# Sheet1.net
KiCad netlist of a schematic drawn in Altium Designer
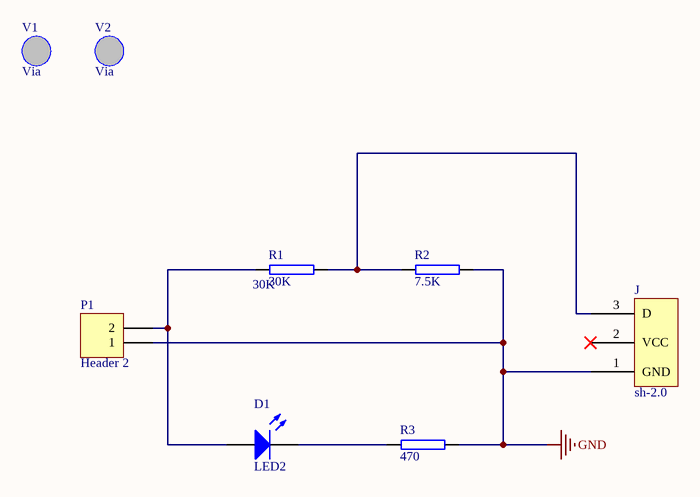
[diagram p0: Sheet1.SchDoc]

(export (version "E")
  (design (tool "Eeschema 10.0.6"))
  (components
    (comp (ref "D1")
      (value "LED2")
      (footprint "3.2X1.6X1.1")
      (description "Typical RED, GREEN, YELLOW, AMBER GaAs LED")
      (fields (field (name "PUBLISHER") "Altium Limited"))
      (libsource (lib "Miscellaneous Devices") (part "LED2"))
    )
    (comp (ref "J") (value "sh-2.0") (footprint "sh-2.0") (libsource (lib "zhangchong") (part "sh-2.0")))
    (comp (ref "P1")
      (value "Header 2")
      (footprint "DIP2")
      (description "Header, 2-Pin")
      (fields (field (name "PUBLISHER") "Altium Limited"))
      (libsource (lib "Miscellaneous Connectors") (part "Header 2"))
    )
    (comp (ref "R1")
      (value "30K")
      (footprint "Miscellaneous Devices:1608[0603]")
      (fields (field (name "ALTIUM_UNNAMED_1") "30K"))
      (libsource (lib "gupeng_sch") (part "RES"))
    )
    (comp (ref "R2")
      (value "7.5K")
      (footprint "Miscellaneous Devices:1608[0603]")
      (libsource (lib "gupeng_sch") (part "RES"))
    )
    (comp (ref "R3")
      (value "470")
      (footprint "Miscellaneous Devices:1608[0603]")
      (libsource (lib "gupeng_sch") (part "RES"))
    )
    (comp (ref "V1") (value "Via") (footprint "zhangchong:Via") (libsource (lib "zhaoyujiu") (part "Via")))
    (comp (ref "V2") (value "Via") (footprint "zhangchong:Via") (libsource (lib "zhaoyujiu") (part "Via")))
  )
  (nets
    (net (code "1") (name "GND") (class "Default")
      (node (ref "J") (pin "1") (pinfunction "GND_1") (pintype "passive"))
      (node (ref "P1") (pin "1") (pinfunction "1_1") (pintype "passive"))
      (node (ref "R2") (pin "2") (pinfunction "2_2") (pintype "passive"))
      (node (ref "R3") (pin "2") (pinfunction "2_2") (pintype "passive"))
    )
    (net (code "2") (name "Net-(D1-A)") (class "Default")
      (node (ref "D1") (pin "1") (pinfunction "A_1") (pintype "passive"))
      (node (ref "P1") (pin "2") (pinfunction "2_2") (pintype "passive"))
      (node (ref "R1") (pin "1") (pinfunction "1_1") (pintype "passive"))
    )
    (net (code "3") (name "Net-(D1-K)") (class "Default")
      (node (ref "D1") (pin "2") (pinfunction "K_2") (pintype "passive"))
      (node (ref "R3") (pin "1") (pinfunction "1_1") (pintype "passive"))
    )
    (net (code "4") (name "Net-(J-D)") (class "Default")
      (node (ref "J") (pin "3") (pinfunction "D_3") (pintype "passive"))
      (node (ref "R1") (pin "2") (pinfunction "2_2") (pintype "passive"))
      (node (ref "R2") (pin "1") (pinfunction "1_1") (pintype "passive"))
    )
    (net (code "5") (name "unconnected-(J-VCC-Pad2)") (class "Default")
      (node (ref "J") (pin "2") (pinfunction "VCC_2") (pintype "passive+no_connect"))
    )
  )
)
